# powerboard-no-gnd-plane.net
KiCad netlist of a schematic drawn in EAGLE
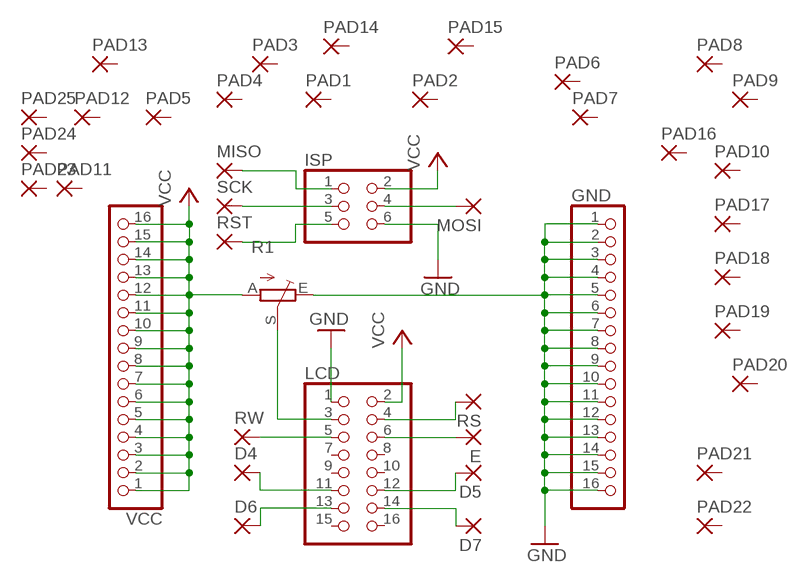
[diagram p0: schematic, sheet 1]

(export (version "E")
  (design (tool "Eeschema 10.0.6"))
  (components
    (comp (ref "D4")
      (value "2,54/1,1")
      (footprint "eagle-import:2,54_1,1")
      (libsource (lib "eagle-import") (part "2,54/1,1"))
    )
    (comp (ref "D5")
      (value "2,54/1,1")
      (footprint "eagle-import:2,54_1,1")
      (libsource (lib "eagle-import") (part "2,54/1,1"))
    )
    (comp (ref "D6")
      (value "2,54/1,1")
      (footprint "eagle-import:2,54_1,1")
      (libsource (lib "eagle-import") (part "2,54/1,1"))
    )
    (comp (ref "D7")
      (value "2,54/1,1")
      (footprint "eagle-import:2,54_1,1")
      (libsource (lib "eagle-import") (part "2,54/1,1"))
    )
    (comp (ref "E")
      (value "2,54/1,1")
      (footprint "eagle-import:2,54_1,1")
      (libsource (lib "eagle-import") (part "2,54/1,1"))
    )
    (comp (ref "GND")
      (value "PINHD-1X16")
      (footprint "eagle-import:1X16")
      (libsource (lib "eagle-import") (part "PINHD-1X16"))
    )
    (comp (ref "ISP")
      (value "PINHD-2X3")
      (footprint "eagle-import:2X03")
      (libsource (lib "eagle-import") (part "PINHD-2X3"))
    )
    (comp (ref "LCD")
      (value "PINHD-2X8")
      (footprint "eagle-import:2X08")
      (libsource (lib "eagle-import") (part "PINHD-2X8"))
    )
    (comp (ref "MISO")
      (value "2,54/1,1")
      (footprint "eagle-import:2,54_1,1")
      (libsource (lib "eagle-import") (part "2,54/1,1"))
    )
    (comp (ref "MOSI")
      (value "2,54/1,1")
      (footprint "eagle-import:2,54_1,1")
      (libsource (lib "eagle-import") (part "2,54/1,1"))
    )
    (comp (ref "PAD1")
      (value "2,15/1,0")
      (footprint "eagle-import:2,15_1,0")
      (libsource (lib "eagle-import") (part "2,15/1,0"))
    )
    (comp (ref "PAD2")
      (value "2,15/1,0")
      (footprint "eagle-import:2,15_1,0")
      (libsource (lib "eagle-import") (part "2,15/1,0"))
    )
    (comp (ref "PAD3")
      (value "2,15/1,0")
      (footprint "eagle-import:2,15_1,0")
      (libsource (lib "eagle-import") (part "2,15/1,0"))
    )
    (comp (ref "PAD4")
      (value "2,15/1,0")
      (footprint "eagle-import:2,15_1,0")
      (libsource (lib "eagle-import") (part "2,15/1,0"))
    )
    (comp (ref "PAD5")
      (value "2,15/1,0")
      (footprint "eagle-import:2,15_1,0")
      (libsource (lib "eagle-import") (part "2,15/1,0"))
    )
    (comp (ref "PAD6")
      (value "2,15/1,0")
      (footprint "eagle-import:2,15_1,0")
      (libsource (lib "eagle-import") (part "2,15/1,0"))
    )
    (comp (ref "PAD7")
      (value "2,15/1,0")
      (footprint "eagle-import:2,15_1,0")
      (libsource (lib "eagle-import") (part "2,15/1,0"))
    )
    (comp (ref "PAD8")
      (value "2,15/1,0")
      (footprint "eagle-import:2,15_1,0")
      (libsource (lib "eagle-import") (part "2,15/1,0"))
    )
    (comp (ref "PAD9")
      (value "2,15/1,0")
      (footprint "eagle-import:2,15_1,0")
      (libsource (lib "eagle-import") (part "2,15/1,0"))
    )
    (comp (ref "PAD10")
      (value "2,15/1,0")
      (footprint "eagle-import:2,15_1,0")
      (libsource (lib "eagle-import") (part "2,15/1,0"))
    )
    (comp (ref "PAD11")
      (value "2,15/1,0")
      (footprint "eagle-import:2,15_1,0")
      (libsource (lib "eagle-import") (part "2,15/1,0"))
    )
    (comp (ref "PAD12")
      (value "2,15/1,0")
      (footprint "eagle-import:2,15_1,0")
      (libsource (lib "eagle-import") (part "2,15/1,0"))
    )
    (comp (ref "PAD13")
      (value "2,15/1,0")
      (footprint "eagle-import:2,15_1,0")
      (libsource (lib "eagle-import") (part "2,15/1,0"))
    )
    (comp (ref "PAD14")
      (value "2,15/1,0")
      (footprint "eagle-import:2,15_1,0")
      (libsource (lib "eagle-import") (part "2,15/1,0"))
    )
    (comp (ref "PAD15")
      (value "2,15/1,0")
      (footprint "eagle-import:2,15_1,0")
      (libsource (lib "eagle-import") (part "2,15/1,0"))
    )
    (comp (ref "PAD16")
      (value "2,15/1,0")
      (footprint "eagle-import:2,15_1,0")
      (libsource (lib "eagle-import") (part "2,15/1,0"))
    )
    (comp (ref "PAD17")
      (value "2,15/1,0")
      (footprint "eagle-import:2,15_1,0")
      (libsource (lib "eagle-import") (part "2,15/1,0"))
    )
    (comp (ref "PAD18")
      (value "2,15/1,0")
      (footprint "eagle-import:2,15_1,0")
      (libsource (lib "eagle-import") (part "2,15/1,0"))
    )
    (comp (ref "PAD19")
      (value "2,15/1,0")
      (footprint "eagle-import:2,15_1,0")
      (libsource (lib "eagle-import") (part "2,15/1,0"))
    )
    (comp (ref "PAD20")
      (value "2,15/1,0")
      (footprint "eagle-import:2,15_1,0")
      (libsource (lib "eagle-import") (part "2,15/1,0"))
    )
    (comp (ref "PAD21")
      (value "2,15/1,0")
      (footprint "eagle-import:2,15_1,0")
      (libsource (lib "eagle-import") (part "2,15/1,0"))
    )
    (comp (ref "PAD22")
      (value "2,15/1,0")
      (footprint "eagle-import:2,15_1,0")
      (libsource (lib "eagle-import") (part "2,15/1,0"))
    )
    (comp (ref "PAD23")
      (value "2,15/1,0")
      (footprint "eagle-import:2,15_1,0")
      (libsource (lib "eagle-import") (part "2,15/1,0"))
    )
    (comp (ref "PAD24")
      (value "2,15/1,0")
      (footprint "eagle-import:2,15_1,0")
      (libsource (lib "eagle-import") (part "2,15/1,0"))
    )
    (comp (ref "PAD25")
      (value "2,15/1,0")
      (footprint "eagle-import:2,15_1,0")
      (libsource (lib "eagle-import") (part "2,15/1,0"))
    )
    (comp (ref "R1")
      (value "TRIM_EU-LI10")
      (footprint "eagle-import:LI10")
      (libsource (lib "eagle-import") (part "TRIM_EU-LI10"))
    )
    (comp (ref "RS")
      (value "2,54/1,1")
      (footprint "eagle-import:2,54_1,1")
      (libsource (lib "eagle-import") (part "2,54/1,1"))
    )
    (comp (ref "RST")
      (value "2,54/1,1")
      (footprint "eagle-import:2,54_1,1")
      (libsource (lib "eagle-import") (part "2,54/1,1"))
    )
    (comp (ref "RW")
      (value "2,54/1,1")
      (footprint "eagle-import:2,54_1,1")
      (libsource (lib "eagle-import") (part "2,54/1,1"))
    )
    (comp (ref "SCK")
      (value "2,54/1,1")
      (footprint "eagle-import:2,54_1,1")
      (libsource (lib "eagle-import") (part "2,54/1,1"))
    )
    (comp (ref "VCC")
      (value "PINHD-1X16")
      (footprint "eagle-import:1X16")
      (libsource (lib "eagle-import") (part "PINHD-1X16"))
    )
  )
  (nets
    (net (code "1") (name "GND") (class "Default")
      (node (ref "GND") (pin "1") (pinfunction "1_1") (pintype "passive"))
      (node (ref "GND") (pin "10") (pinfunction "10_10") (pintype "passive"))
      (node (ref "GND") (pin "11") (pinfunction "11_11") (pintype "passive"))
      (node (ref "GND") (pin "12") (pinfunction "12_12") (pintype "passive"))
      (node (ref "GND") (pin "13") (pinfunction "13_13") (pintype "passive"))
      (node (ref "GND") (pin "14") (pinfunction "14_14") (pintype "passive"))
      (node (ref "GND") (pin "15") (pinfunction "15_15") (pintype "passive"))
      (node (ref "GND") (pin "16") (pinfunction "16_16") (pintype "passive"))
      (node (ref "GND") (pin "2") (pinfunction "2_2") (pintype "passive"))
      (node (ref "GND") (pin "3") (pinfunction "3_3") (pintype "passive"))
      (node (ref "GND") (pin "4") (pinfunction "4_4") (pintype "passive"))
      (node (ref "GND") (pin "5") (pinfunction "5_5") (pintype "passive"))
      (node (ref "GND") (pin "6") (pinfunction "6_6") (pintype "passive"))
      (node (ref "GND") (pin "7") (pinfunction "7_7") (pintype "passive"))
      (node (ref "GND") (pin "8") (pinfunction "8_8") (pintype "passive"))
      (node (ref "GND") (pin "9") (pinfunction "9_9") (pintype "passive"))
      (node (ref "ISP") (pin "6") (pinfunction "6_6") (pintype "passive"))
      (node (ref "LCD") (pin "1") (pinfunction "1_1") (pintype "passive"))
      (node (ref "R1") (pin "E") (pinfunction "E_E") (pintype "passive"))
    )
    (net (code "2") (name "Net-(D4-P)") (class "Default")
      (node (ref "D4") (pin "1") (pinfunction "P_1") (pintype "passive"))
      (node (ref "LCD") (pin "11") (pinfunction "11_11") (pintype "passive"))
    )
    (net (code "3") (name "Net-(D5-P)") (class "Default")
      (node (ref "D5") (pin "1") (pinfunction "P_1") (pintype "passive"))
      (node (ref "LCD") (pin "12") (pinfunction "12_12") (pintype "passive"))
    )
    (net (code "4") (name "Net-(D6-P)") (class "Default")
      (node (ref "D6") (pin "1") (pinfunction "P_1") (pintype "passive"))
      (node (ref "LCD") (pin "13") (pinfunction "13_13") (pintype "passive"))
    )
    (net (code "5") (name "Net-(D7-P)") (class "Default")
      (node (ref "D7") (pin "1") (pinfunction "P_1") (pintype "passive"))
      (node (ref "LCD") (pin "14") (pinfunction "14_14") (pintype "passive"))
    )
    (net (code "6") (name "Net-(E-P)") (class "Default")
      (node (ref "E") (pin "1") (pinfunction "P_1") (pintype "passive"))
      (node (ref "LCD") (pin "6") (pinfunction "6_6") (pintype "passive"))
    )
    (net (code "7") (name "Net-(LCD-Pad3)") (class "Default")
      (node (ref "LCD") (pin "3") (pinfunction "3_3") (pintype "passive"))
      (node (ref "R1") (pin "S") (pinfunction "S_S") (pintype "passive"))
    )
    (net (code "8") (name "Net-(MISO-P)") (class "Default")
      (node (ref "ISP") (pin "1") (pinfunction "1_1") (pintype "passive"))
      (node (ref "MISO") (pin "1") (pinfunction "P_1") (pintype "passive"))
    )
    (net (code "9") (name "Net-(MOSI-P)") (class "Default")
      (node (ref "ISP") (pin "4") (pinfunction "4_4") (pintype "passive"))
      (node (ref "MOSI") (pin "1") (pinfunction "P_1") (pintype "passive"))
    )
    (net (code "10") (name "Net-(RS-P)") (class "Default")
      (node (ref "LCD") (pin "4") (pinfunction "4_4") (pintype "passive"))
      (node (ref "RS") (pin "1") (pinfunction "P_1") (pintype "passive"))
    )
    (net (code "11") (name "Net-(RST-P)") (class "Default")
      (node (ref "ISP") (pin "5") (pinfunction "5_5") (pintype "passive"))
      (node (ref "RST") (pin "1") (pinfunction "P_1") (pintype "passive"))
    )
    (net (code "12") (name "Net-(RW-P)") (class "Default")
      (node (ref "LCD") (pin "5") (pinfunction "5_5") (pintype "passive"))
      (node (ref "RW") (pin "1") (pinfunction "P_1") (pintype "passive"))
    )
    (net (code "13") (name "Net-(SCK-P)") (class "Default")
      (node (ref "ISP") (pin "3") (pinfunction "3_3") (pintype "passive"))
      (node (ref "SCK") (pin "1") (pinfunction "P_1") (pintype "passive"))
    )
    (net (code "14") (name "VCC") (class "Default")
      (node (ref "ISP") (pin "2") (pinfunction "2_2") (pintype "passive"))
      (node (ref "LCD") (pin "2") (pinfunction "2_2") (pintype "passive"))
      (node (ref "R1") (pin "A") (pinfunction "A_A") (pintype "passive"))
      (node (ref "VCC") (pin "1") (pinfunction "1_1") (pintype "passive"))
      (node (ref "VCC") (pin "10") (pinfunction "10_10") (pintype "passive"))
      (node (ref "VCC") (pin "11") (pinfunction "11_11") (pintype "passive"))
      (node (ref "VCC") (pin "12") (pinfunction "12_12") (pintype "passive"))
      (node (ref "VCC") (pin "13") (pinfunction "13_13") (pintype "passive"))
      (node (ref "VCC") (pin "14") (pinfunction "14_14") (pintype "passive"))
      (node (ref "VCC") (pin "15") (pinfunction "15_15") (pintype "passive"))
      (node (ref "VCC") (pin "16") (pinfunction "16_16") (pintype "passive"))
      (node (ref "VCC") (pin "2") (pinfunction "2_2") (pintype "passive"))
      (node (ref "VCC") (pin "3") (pinfunction "3_3") (pintype "passive"))
      (node (ref "VCC") (pin "4") (pinfunction "4_4") (pintype "passive"))
      (node (ref "VCC") (pin "5") (pinfunction "5_5") (pintype "passive"))
      (node (ref "VCC") (pin "6") (pinfunction "6_6") (pintype "passive"))
      (node (ref "VCC") (pin "7") (pinfunction "7_7") (pintype "passive"))
      (node (ref "VCC") (pin "8") (pinfunction "8_8") (pintype "passive"))
      (node (ref "VCC") (pin "9") (pinfunction "9_9") (pintype "passive"))
    )
    (net (code "15") (name "unconnected-(LCD-Pad7)") (class "Default")
      (node (ref "LCD") (pin "7") (pinfunction "7_7") (pintype "passive"))
    )
    (net (code "16") (name "unconnected-(LCD-Pad8)") (class "Default")
      (node (ref "LCD") (pin "8") (pinfunction "8_8") (pintype "passive"))
    )
    (net (code "17") (name "unconnected-(LCD-Pad9)") (class "Default")
      (node (ref "LCD") (pin "9") (pinfunction "9_9") (pintype "passive"))
    )
    (net (code "18") (name "unconnected-(LCD-Pad10)") (class "Default")
      (node (ref "LCD") (pin "10") (pinfunction "10_10") (pintype "passive"))
    )
    (net (code "19") (name "unconnected-(LCD-Pad15)") (class "Default")
      (node (ref "LCD") (pin "15") (pinfunction "15_15") (pintype "passive"))
    )
    (net (code "20") (name "unconnected-(LCD-Pad16)") (class "Default")
      (node (ref "LCD") (pin "16") (pinfunction "16_16") (pintype "passive"))
    )
    (net (code "21") (name "unconnected-(PAD1-P-Pad1)") (class "Default")
      (node (ref "PAD1") (pin "1") (pinfunction "P_1") (pintype "passive"))
    )
    (net (code "22") (name "unconnected-(PAD2-P-Pad1)") (class "Default")
      (node (ref "PAD2") (pin "1") (pinfunction "P_1") (pintype "passive"))
    )
    (net (code "23") (name "unconnected-(PAD3-P-Pad1)") (class "Default")
      (node (ref "PAD3") (pin "1") (pinfunction "P_1") (pintype "passive"))
    )
    (net (code "24") (name "unconnected-(PAD4-P-Pad1)") (class "Default")
      (node (ref "PAD4") (pin "1") (pinfunction "P_1") (pintype "passive"))
    )
    (net (code "25") (name "unconnected-(PAD5-P-Pad1)") (class "Default")
      (node (ref "PAD5") (pin "1") (pinfunction "P_1") (pintype "passive"))
    )
    (net (code "26") (name "unconnected-(PAD6-P-Pad1)") (class "Default")
      (node (ref "PAD6") (pin "1") (pinfunction "P_1") (pintype "passive"))
    )
    (net (code "27") (name "unconnected-(PAD7-P-Pad1)") (class "Default")
      (node (ref "PAD7") (pin "1") (pinfunction "P_1") (pintype "passive"))
    )
    (net (code "28") (name "unconnected-(PAD8-P-Pad1)") (class "Default")
      (node (ref "PAD8") (pin "1") (pinfunction "P_1") (pintype "passive"))
    )
    (net (code "29") (name "unconnected-(PAD9-P-Pad1)") (class "Default")
      (node (ref "PAD9") (pin "1") (pinfunction "P_1") (pintype "passive"))
    )
    (net (code "30") (name "unconnected-(PAD10-P-Pad1)") (class "Default")
      (node (ref "PAD10") (pin "1") (pinfunction "P_1") (pintype "passive"))
    )
    (net (code "31") (name "unconnected-(PAD11-P-Pad1)") (class "Default")
      (node (ref "PAD11") (pin "1") (pinfunction "P_1") (pintype "passive"))
    )
    (net (code "32") (name "unconnected-(PAD12-P-Pad1)") (class "Default")
      (node (ref "PAD12") (pin "1") (pinfunction "P_1") (pintype "passive"))
    )
    (net (code "33") (name "unconnected-(PAD13-P-Pad1)") (class "Default")
      (node (ref "PAD13") (pin "1") (pinfunction "P_1") (pintype "passive"))
    )
    (net (code "34") (name "unconnected-(PAD14-P-Pad1)") (class "Default")
      (node (ref "PAD14") (pin "1") (pinfunction "P_1") (pintype "passive"))
    )
    (net (code "35") (name "unconnected-(PAD15-P-Pad1)") (class "Default")
      (node (ref "PAD15") (pin "1") (pinfunction "P_1") (pintype "passive"))
    )
    (net (code "36") (name "unconnected-(PAD16-P-Pad1)") (class "Default")
      (node (ref "PAD16") (pin "1") (pinfunction "P_1") (pintype "passive"))
    )
    (net (code "37") (name "unconnected-(PAD17-P-Pad1)") (class "Default")
      (node (ref "PAD17") (pin "1") (pinfunction "P_1") (pintype "passive"))
    )
    (net (code "38") (name "unconnected-(PAD18-P-Pad1)") (class "Default")
      (node (ref "PAD18") (pin "1") (pinfunction "P_1") (pintype "passive"))
    )
    (net (code "39") (name "unconnected-(PAD19-P-Pad1)") (class "Default")
      (node (ref "PAD19") (pin "1") (pinfunction "P_1") (pintype "passive"))
    )
    (net (code "40") (name "unconnected-(PAD20-P-Pad1)") (class "Default")
      (node (ref "PAD20") (pin "1") (pinfunction "P_1") (pintype "passive"))
    )
    (net (code "41") (name "unconnected-(PAD21-P-Pad1)") (class "Default")
      (node (ref "PAD21") (pin "1") (pinfunction "P_1") (pintype "passive"))
    )
    (net (code "42") (name "unconnected-(PAD22-P-Pad1)") (class "Default")
      (node (ref "PAD22") (pin "1") (pinfunction "P_1") (pintype "passive"))
    )
    (net (code "43") (name "unconnected-(PAD23-P-Pad1)") (class "Default")
      (node (ref "PAD23") (pin "1") (pinfunction "P_1") (pintype "passive"))
    )
    (net (code "44") (name "unconnected-(PAD24-P-Pad1)") (class "Default")
      (node (ref "PAD24") (pin "1") (pinfunction "P_1") (pintype "passive"))
    )
    (net (code "45") (name "unconnected-(PAD25-P-Pad1)") (class "Default")
      (node (ref "PAD25") (pin "1") (pinfunction "P_1") (pintype "passive"))
    )
  )
)
